# 4_Connectors.net
KiCad netlist of a schematic drawn in Altium Designer
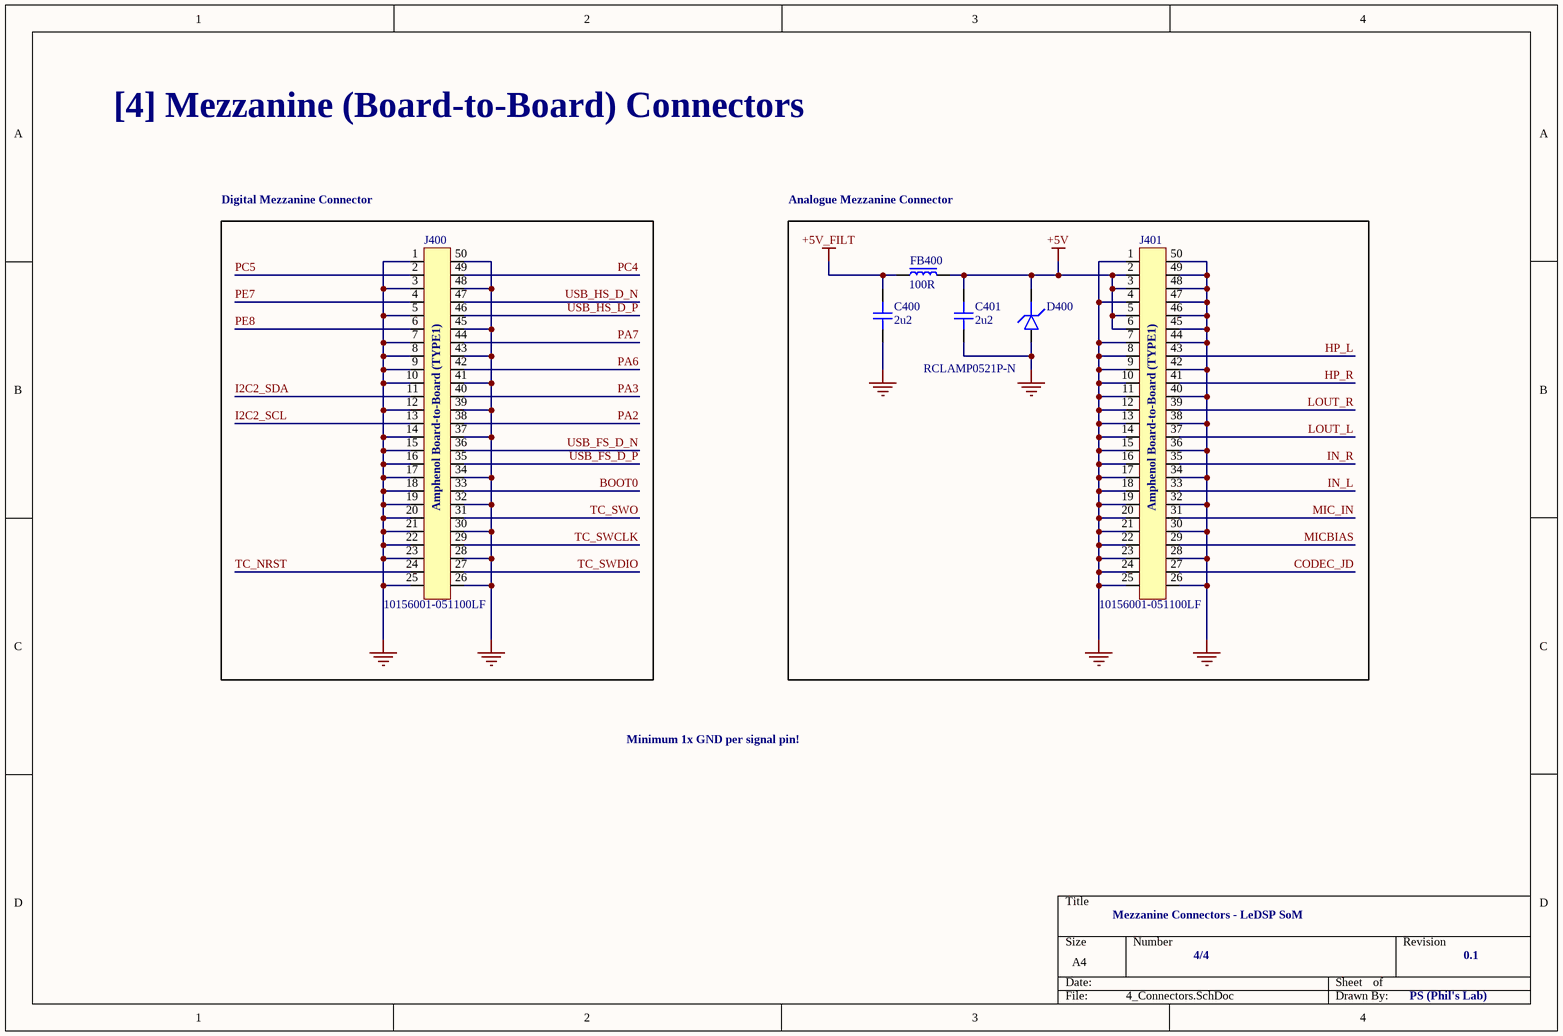
[diagram p0: 4_Connectors.SchDoc]

(export (version "E")
  (design (tool "Eeschema 10.0.6"))
  (components
    (comp (ref "C400")
      (value "2u2")
      (footprint "CAP_0603")
      (description "Capacitor SMD 0603 16V")
      (libsource (lib "Schematic-Lib-PhilsLab") (part "CAP_0603_16V"))
    )
    (comp (ref "C401")
      (value "2u2")
      (footprint "CAP_0603")
      (description "Capacitor SMD 0603 16V")
      (libsource (lib "Schematic-Lib-PhilsLab") (part "CAP_0603_16V"))
    )
    (comp (ref "D400")
      (value "RCLAMP0521P-N")
      (footprint "D_0402")
      (description "Diode TVS / ESD 0402")
      (libsource (lib "Schematic-Lib-PhilsLab") (part "D_TVS_0402"))
    )
    (comp (ref "FB400")
      (value "100R")
      (footprint "FB_0603")
      (description "Ferrite Bead SMD 0603")
      (libsource (lib "Schematic-Lib-PhilsLab") (part "FB_0603"))
    )
    (comp (ref "J400")
      (value "10156001-051100LF")
      (footprint "10156001-051100LF")
      (description "Board-to-Board Connector 0.5mm Pitch 50 Position 2 Row")
      (fields (field (name "MANUFACTURER") "Amphenol FCI"))
      (libsource (lib "Schematic-Lib-PhilsLab") (part "10156001-051100LF"))
    )
    (comp (ref "J401")
      (value "10156001-051100LF")
      (footprint "10156001-051100LF")
      (description "Board-to-Board Connector 0.5mm Pitch 50 Position 2 Row")
      (fields (field (name "MANUFACTURER") "Amphenol FCI"))
      (libsource (lib "Schematic-Lib-PhilsLab") (part "10156001-051100LF"))
    )
  )
  (nets
    (net (code "1") (name "+5V") (class "Default")
      (node (ref "C401") (pin "2") (pinfunction "2_2") (pintype "passive"))
      (node (ref "D400") (pin "K") (pinfunction "K_K") (pintype "passive"))
      (node (ref "FB400") (pin "2") (pinfunction "2_2") (pintype "passive"))
      (node (ref "J401") (pin "2") (pintype "passive"))
      (node (ref "J401") (pin "3") (pintype "passive"))
      (node (ref "J401") (pin "5") (pintype "passive"))
      (node (ref "J401") (pin "6") (pintype "passive"))
    )
    (net (code "2") (name "+5V_FILT") (class "Default")
      (node (ref "C400") (pin "2") (pinfunction "2_2") (pintype "passive"))
      (node (ref "FB400") (pin "1") (pinfunction "1_1") (pintype "passive"))
    )
    (net (code "3") (name "/BOOT0") (class "Default") (node (ref "J400") (pin "33") (pintype "passive")))
    (net (code "4") (name "/CODEC_JD") (class "Default") (node (ref "J401") (pin "27") (pintype "passive")))
    (net (code "5") (name "/HP_L") (class "Default") (node (ref "J401") (pin "43") (pintype "passive")))
    (net (code "6") (name "/HP_R") (class "Default") (node (ref "J401") (pin "41") (pintype "passive")))
    (net (code "7") (name "/I2C2_SCL") (class "Default") (node (ref "J400") (pin "13") (pintype "passive")))
    (net (code "8") (name "/I2C2_SDA") (class "Default") (node (ref "J400") (pin "11") (pintype "passive")))
    (net (code "9") (name "/IN_L") (class "Default") (node (ref "J401") (pin "33") (pintype "passive")))
    (net (code "10") (name "/IN_R") (class "Default") (node (ref "J401") (pin "35") (pintype "passive")))
    (net (code "11") (name "/LOUT_L") (class "Default") (node (ref "J401") (pin "37") (pintype "passive")))
    (net (code "12") (name "/LOUT_R") (class "Default") (node (ref "J401") (pin "39") (pintype "passive")))
    (net (code "13") (name "/MICBIAS") (class "Default") (node (ref "J401") (pin "29") (pintype "passive")))
    (net (code "14") (name "/MIC_IN") (class "Default") (node (ref "J401") (pin "31") (pintype "passive")))
    (net (code "15") (name "/PA2") (class "Default") (node (ref "J400") (pin "38") (pintype "passive")))
    (net (code "16") (name "/PA3") (class "Default") (node (ref "J400") (pin "40") (pintype "passive")))
    (net (code "17") (name "/PA6") (class "Default") (node (ref "J400") (pin "42") (pintype "passive")))
    (net (code "18") (name "/PA7") (class "Default") (node (ref "J400") (pin "44") (pintype "passive")))
    (net (code "19") (name "/PC4") (class "Default") (node (ref "J400") (pin "49") (pintype "passive")))
    (net (code "20") (name "/PC5") (class "Default") (node (ref "J400") (pin "2") (pintype "passive")))
    (net (code "21") (name "/PE7") (class "Default") (node (ref "J400") (pin "4") (pintype "passive")))
    (net (code "22") (name "/PE8") (class "Default") (node (ref "J400") (pin "6") (pintype "passive")))
    (net (code "23") (name "/TC_NRST") (class "Default") (node (ref "J400") (pin "24") (pintype "passive")))
    (net (code "24") (name "/TC_SWCLK") (class "Default") (node (ref "J400") (pin "29") (pintype "passive")))
    (net (code "25") (name "/TC_SWDIO") (class "Default") (node (ref "J400") (pin "27") (pintype "passive")))
    (net (code "26") (name "/TC_SWO") (class "Default") (node (ref "J400") (pin "31") (pintype "passive")))
    (net (code "27") (name "/USB_FS_D_N") (class "Default")
      (node (ref "J400") (pin "36") (pintype "passive"))
    )
    (net (code "28") (name "/USB_FS_D_P") (class "Default")
      (node (ref "J400") (pin "35") (pintype "passive"))
    )
    (net (code "29") (name "/USB_HS_D_N") (class "Default")
      (node (ref "J400") (pin "47") (pintype "passive"))
    )
    (net (code "30") (name "/USB_HS_D_P") (class "Default")
      (node (ref "J400") (pin "46") (pintype "passive"))
    )
    (net (code "31") (name "GND") (class "Default")
      (node (ref "C400") (pin "1") (pinfunction "1_1") (pintype "passive"))
      (node (ref "C401") (pin "1") (pinfunction "1_1") (pintype "passive"))
      (node (ref "D400") (pin "A") (pinfunction "A_A") (pintype "passive"))
      (node (ref "J400") (pin "1") (pintype "passive"))
      (node (ref "J400") (pin "10") (pintype "passive"))
      (node (ref "J400") (pin "12") (pintype "passive"))
      (node (ref "J400") (pin "14") (pintype "passive"))
      (node (ref "J400") (pin "15") (pintype "passive"))
      (node (ref "J400") (pin "16") (pintype "passive"))
      (node (ref "J400") (pin "17") (pintype "passive"))
      (node (ref "J400") (pin "18") (pintype "passive"))
      (node (ref "J400") (pin "19") (pintype "passive"))
      (node (ref "J400") (pin "20") (pintype "passive"))
      (node (ref "J400") (pin "21") (pintype "passive"))
      (node (ref "J400") (pin "22") (pintype "passive"))
      (node (ref "J400") (pin "23") (pintype "passive"))
      (node (ref "J400") (pin "25") (pintype "passive"))
      (node (ref "J400") (pin "26") (pintype "passive"))
      (node (ref "J400") (pin "28") (pintype "passive"))
      (node (ref "J400") (pin "3") (pintype "passive"))
      (node (ref "J400") (pin "30") (pintype "passive"))
      (node (ref "J400") (pin "32") (pintype "passive"))
      (node (ref "J400") (pin "34") (pintype "passive"))
      (node (ref "J400") (pin "37") (pintype "passive"))
      (node (ref "J400") (pin "39") (pintype "passive"))
      (node (ref "J400") (pin "41") (pintype "passive"))
      (node (ref "J400") (pin "43") (pintype "passive"))
      (node (ref "J400") (pin "45") (pintype "passive"))
      (node (ref "J400") (pin "48") (pintype "passive"))
      (node (ref "J400") (pin "5") (pintype "passive"))
      (node (ref "J400") (pin "50") (pintype "passive"))
      (node (ref "J400") (pin "7") (pintype "passive"))
      (node (ref "J400") (pin "8") (pintype "passive"))
      (node (ref "J400") (pin "9") (pintype "passive"))
      (node (ref "J401") (pin "1") (pintype "passive"))
      (node (ref "J401") (pin "10") (pintype "passive"))
      (node (ref "J401") (pin "11") (pintype "passive"))
      (node (ref "J401") (pin "12") (pintype "passive"))
      (node (ref "J401") (pin "13") (pintype "passive"))
      (node (ref "J401") (pin "14") (pintype "passive"))
      (node (ref "J401") (pin "15") (pintype "passive"))
      (node (ref "J401") (pin "16") (pintype "passive"))
      (node (ref "J401") (pin "17") (pintype "passive"))
      (node (ref "J401") (pin "18") (pintype "passive"))
      (node (ref "J401") (pin "19") (pintype "passive"))
      (node (ref "J401") (pin "20") (pintype "passive"))
      (node (ref "J401") (pin "21") (pintype "passive"))
      (node (ref "J401") (pin "22") (pintype "passive"))
      (node (ref "J401") (pin "23") (pintype "passive"))
      (node (ref "J401") (pin "24") (pintype "passive"))
      (node (ref "J401") (pin "25") (pintype "passive"))
      (node (ref "J401") (pin "26") (pintype "passive"))
      (node (ref "J401") (pin "28") (pintype "passive"))
      (node (ref "J401") (pin "30") (pintype "passive"))
      (node (ref "J401") (pin "32") (pintype "passive"))
      (node (ref "J401") (pin "34") (pintype "passive"))
      (node (ref "J401") (pin "36") (pintype "passive"))
      (node (ref "J401") (pin "38") (pintype "passive"))
      (node (ref "J401") (pin "4") (pintype "passive"))
      (node (ref "J401") (pin "40") (pintype "passive"))
      (node (ref "J401") (pin "42") (pintype "passive"))
      (node (ref "J401") (pin "44") (pintype "passive"))
      (node (ref "J401") (pin "45") (pintype "passive"))
      (node (ref "J401") (pin "46") (pintype "passive"))
      (node (ref "J401") (pin "47") (pintype "passive"))
      (node (ref "J401") (pin "48") (pintype "passive"))
      (node (ref "J401") (pin "49") (pintype "passive"))
      (node (ref "J401") (pin "50") (pintype "passive"))
      (node (ref "J401") (pin "7") (pintype "passive"))
      (node (ref "J401") (pin "8") (pintype "passive"))
      (node (ref "J401") (pin "9") (pintype "passive"))
    )
  )
)
